# 05_-_DEBUGGING_PROGRAMMING.net
KiCad netlist of a schematic drawn in Altium Designer
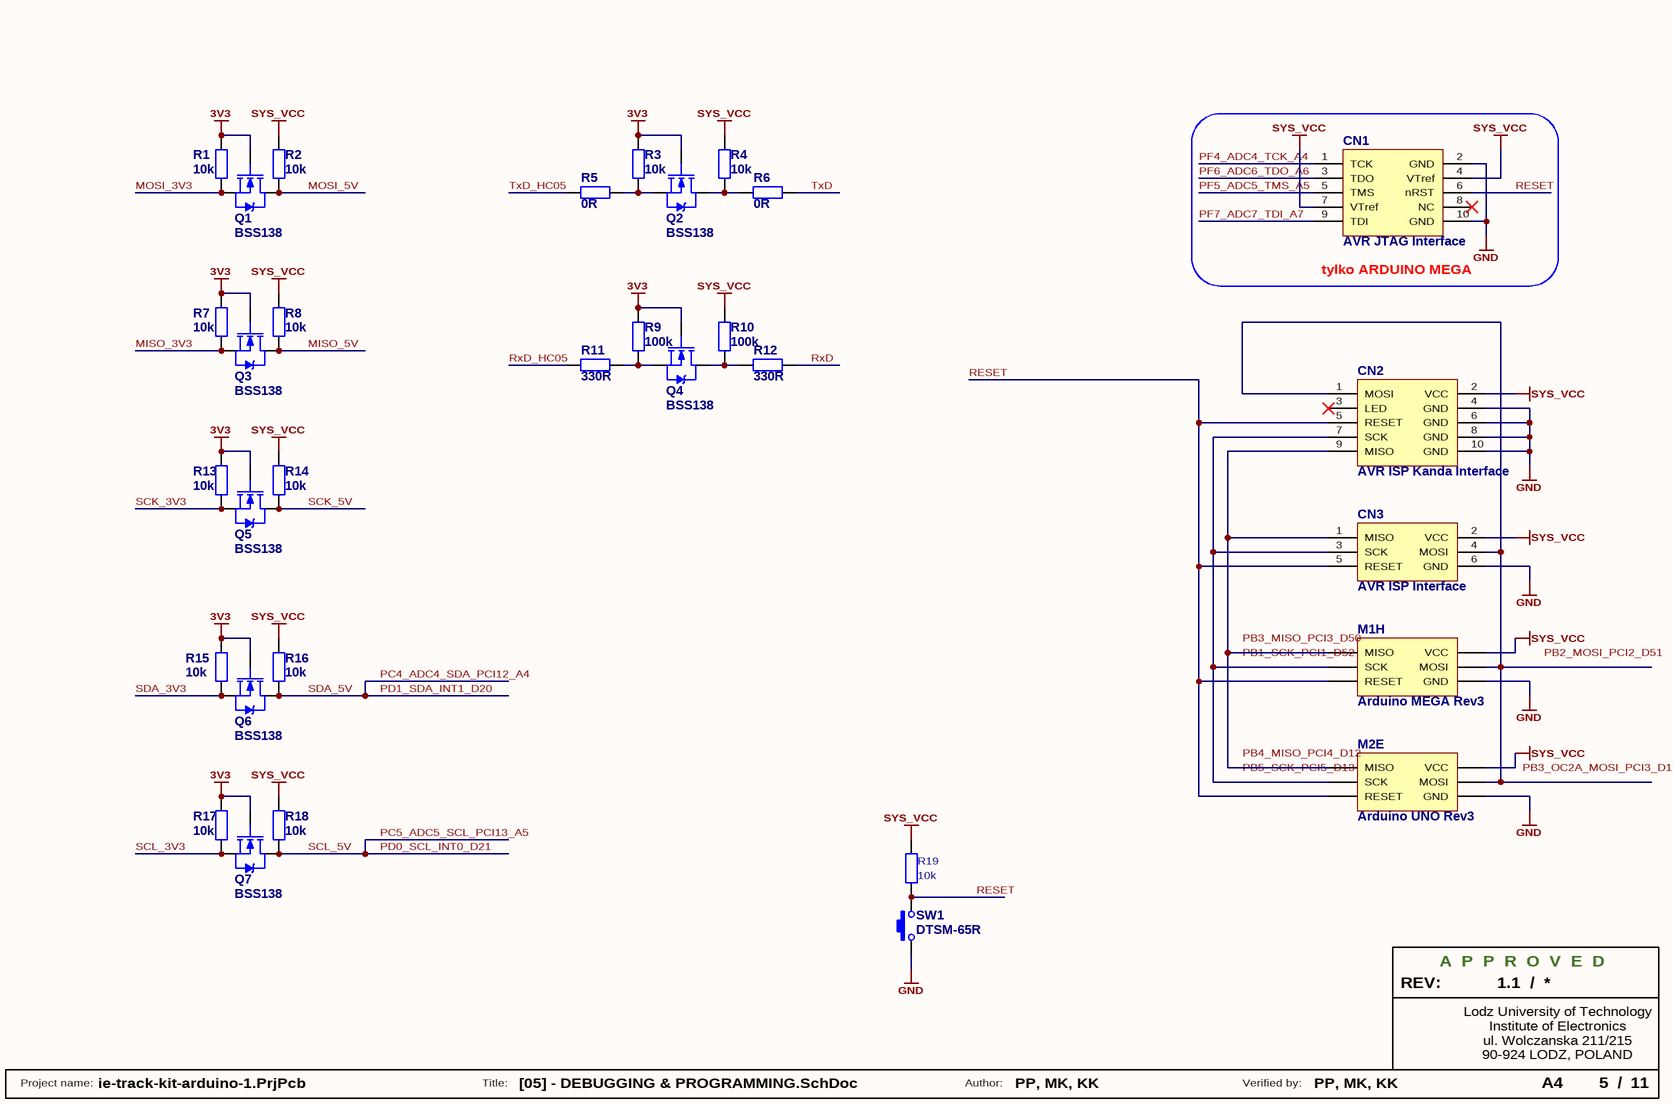
[diagram p0: [05] - DEBUGGING & PROGRAMMING.SchDoc]

(export (version "E")
  (design (tool "Eeschema 10.0.6"))
  (components
    (comp (ref "CN1")
      (value "AVR JTAG Interface")
      (footprint "IDC10")
      (description "JTAG Header for AVR MCU's")
      (libsource (lib "mcu_prog_and_debug_connectors") (part "AVR JTAG Interface"))
    )
    (comp (ref "CN2")
      (value "AVR ISP Kanda Interface")
      (footprint "IDC10")
      (description "Kanda ISP Programming Header for AVR MCU's")
      (libsource (lib "mcu_prog_and_debug_connectors") (part "AVR ISP Kanda Interface"))
    )
    (comp (ref "CN3")
      (value "AVR ISP Interface")
      (footprint "IDC6")
      (description "ISP Programming Header for AVR MCU's")
      (libsource (lib "mcu_prog_and_debug_connectors") (part "AVR ISP Interface"))
    )
    (comp (ref "M1")
      (value "Arduino MEGA Rev3")
      (footprint "Arduino_MEGA_UPSIDE_DOWN")
      (description "Arduino MEGA Rev3 Board")
      (libsource (lib "mcu_modules") (part "Arduino MEGA Rev3"))
    )
    (comp (ref "M2")
      (value "Arduino UNO Rev3")
      (footprint "Arduino_UNO_UPSIDE_DOWN")
      (description "Arduino UNO Rev3 Board")
      (libsource (lib "mcu_modules") (part "Arduino UNO Rev3"))
    )
    (comp (ref "Q1")
      (value "BSS138")
      (footprint "SOT-23")
      (description "N-Channel Enhancement Mode Vertical DMOS FET")
      (fields (field (name "PUBLISHER") "Altium Limited"))
      (libsource (lib "transistors_other") (part "BSS138"))
    )
    (comp (ref "Q2")
      (value "BSS138")
      (footprint "SOT-23")
      (description "N-Channel Enhancement Mode Vertical DMOS FET")
      (fields (field (name "PUBLISHER") "Altium Limited"))
      (libsource (lib "transistors_mos") (part "BSS138"))
    )
    (comp (ref "Q3")
      (value "BSS138")
      (footprint "SOT-23")
      (description "N-Channel Enhancement Mode Vertical DMOS FET")
      (fields (field (name "PUBLISHER") "Altium Limited"))
      (libsource (lib "transistors_other") (part "BSS138"))
    )
    (comp (ref "Q4")
      (value "BSS138")
      (footprint "SOT-23")
      (description "N-Channel Enhancement Mode Vertical DMOS FET")
      (fields (field (name "PUBLISHER") "Altium Limited"))
      (libsource (lib "transistors_mos") (part "BSS138"))
    )
    (comp (ref "Q5")
      (value "BSS138")
      (footprint "SOT-23")
      (description "N-Channel Enhancement Mode Vertical DMOS FET")
      (fields (field (name "PUBLISHER") "Altium Limited"))
      (libsource (lib "transistors_other") (part "BSS138"))
    )
    (comp (ref "Q6")
      (value "BSS138")
      (footprint "SOT-23")
      (description "N-Channel Enhancement Mode Vertical DMOS FET")
      (fields (field (name "PUBLISHER") "Altium Limited"))
      (libsource (lib "transistors_other") (part "BSS138"))
    )
    (comp (ref "Q7")
      (value "BSS138")
      (footprint "SOT-23")
      (description "N-Channel Enhancement Mode Vertical DMOS FET")
      (fields (field (name "PUBLISHER") "Altium Limited"))
      (libsource (lib "transistors_other") (part "BSS138"))
    )
    (comp (ref "R1")
      (value "10k")
      (footprint "R0805")
      (description "Resistor")
      (libsource (lib "resistors") (part "Res"))
    )
    (comp (ref "R2")
      (value "10k")
      (footprint "R0805")
      (description "Resistor")
      (libsource (lib "resistors") (part "Res"))
    )
    (comp (ref "R3")
      (value "10k")
      (footprint "R0805")
      (description "Resistor")
      (libsource (lib "") (part "Res_2"))
    )
    (comp (ref "R4")
      (value "10k")
      (footprint "R0805")
      (description "Resistor")
      (libsource (lib "") (part "Res_2"))
    )
    (comp (ref "R5")
      (value "0R")
      (footprint "R0805")
      (description "Resistor")
      (libsource (lib "") (part "Res_1"))
    )
    (comp (ref "R6")
      (value "0R")
      (footprint "R0805")
      (description "Resistor")
      (libsource (lib "") (part "Res_1"))
    )
    (comp (ref "R7")
      (value "10k")
      (footprint "R0805")
      (description "Resistor")
      (libsource (lib "resistors") (part "Res"))
    )
    (comp (ref "R8")
      (value "10k")
      (footprint "R0805")
      (description "Resistor")
      (libsource (lib "resistors") (part "Res"))
    )
    (comp (ref "R9")
      (value "100k")
      (footprint "R0805")
      (description "Resistor")
      (libsource (lib "") (part "Res_2"))
    )
    (comp (ref "R10")
      (value "100k")
      (footprint "R0805")
      (description "Resistor")
      (libsource (lib "") (part "Res_2"))
    )
    (comp (ref "R11")
      (value "330R")
      (footprint "R0805")
      (description "Resistor")
      (libsource (lib "") (part "Res_1"))
    )
    (comp (ref "R12")
      (value "330R")
      (footprint "R0805")
      (description "Resistor")
      (libsource (lib "") (part "Res_1"))
    )
    (comp (ref "R13")
      (value "10k")
      (footprint "R0805")
      (description "Resistor")
      (libsource (lib "resistors") (part "Res"))
    )
    (comp (ref "R14")
      (value "10k")
      (footprint "R0805")
      (description "Resistor")
      (libsource (lib "resistors") (part "Res"))
    )
    (comp (ref "R15")
      (value "10k")
      (footprint "R0805")
      (description "Resistor")
      (libsource (lib "resistors") (part "Res"))
    )
    (comp (ref "R16")
      (value "10k")
      (footprint "R0805")
      (description "Resistor")
      (libsource (lib "resistors") (part "Res"))
    )
    (comp (ref "R17")
      (value "10k")
      (footprint "R0805")
      (description "Resistor")
      (libsource (lib "resistors") (part "Res"))
    )
    (comp (ref "R18")
      (value "10k")
      (footprint "R0805")
      (description "Resistor")
      (libsource (lib "resistors") (part "Res"))
    )
    (comp (ref "R19")
      (value "10k")
      (footprint "R0805")
      (description "Resistor")
      (libsource (lib "") (part "Res_3"))
    )
    (comp (ref "SW1")
      (value "DTSM-65R")
      (footprint "DTSM-65R")
      (description "DIPTRONICS Red 6x6mm SMD Tactile SPST-NO Switch")
      (libsource (lib "microswitches") (part "DTSM-65R"))
    )
  )
  (nets
    (net (code "1") (name "/MISO_3V3") (class "Default")
      (node (ref "Q3") (pin "2") (pinfunction "S_2") (pintype "passive"))
      (node (ref "R7") (pin "1") (pinfunction "1_1") (pintype "passive"))
    )
    (net (code "2") (name "/MISO_5V") (class "Default")
      (node (ref "Q3") (pin "3") (pinfunction "D_3") (pintype "passive"))
      (node (ref "R8") (pin "1") (pinfunction "1_1") (pintype "passive"))
    )
    (net (code "3") (name "/MOSI_3V3") (class "Default")
      (node (ref "Q1") (pin "2") (pinfunction "S_2") (pintype "passive"))
      (node (ref "R1") (pin "1") (pinfunction "1_1") (pintype "passive"))
    )
    (net (code "4") (name "/MOSI_5V") (class "Default")
      (node (ref "Q1") (pin "3") (pinfunction "D_3") (pintype "passive"))
      (node (ref "R2") (pin "1") (pinfunction "1_1") (pintype "passive"))
    )
    (net (code "11") (name "/PC4_ADC4_SDA_PCI12_A4") (class "Default")
      (node (ref "Q6") (pin "3") (pinfunction "D_3") (pintype "passive"))
      (node (ref "R16") (pin "1") (pinfunction "1_1") (pintype "passive"))
    )
    (net (code "12") (name "/PC5_ADC5_SCL_PCI13_A5") (class "Default")
      (node (ref "Q7") (pin "3") (pinfunction "D_3") (pintype "passive"))
      (node (ref "R18") (pin "1") (pinfunction "1_1") (pintype "passive"))
    )
    (net (code "13") (name "/PF4_ADC4_TCK_A4") (class "Default")
      (node (ref "CN1") (pin "1") (pinfunction "TCK_1") (pintype "passive"))
    )
    (net (code "14") (name "/PF5_ADC5_TMS_A5") (class "Default")
      (node (ref "CN1") (pin "5") (pinfunction "TMS_5") (pintype "passive"))
    )
    (net (code "15") (name "/PF6_ADC6_TDO_A6") (class "Default")
      (node (ref "CN1") (pin "3") (pinfunction "TDO_3") (pintype "passive"))
    )
    (net (code "16") (name "/PF7_ADC7_TDI_A7") (class "Default")
      (node (ref "CN1") (pin "9") (pinfunction "TDI_9") (pintype "passive"))
    )
    (net (code "17") (name "/RESET") (class "Default")
      (node (ref "CN1") (pin "6") (pinfunction "nRST_6") (pintype "passive"))
      (node (ref "CN2") (pin "5") (pinfunction "RESET_5") (pintype "passive"))
      (node (ref "CN3") (pin "5") (pinfunction "RESET_5") (pintype "passive"))
      (node (ref "M1") (pin "PROG5") (pinfunction "RESET_PROG5") (pintype "passive"))
      (node (ref "M2") (pin "PROG5") (pinfunction "RESET_PROG5") (pintype "passive"))
      (node (ref "R19") (pin "1") (pinfunction "1_1") (pintype "passive"))
      (node (ref "SW1") (pin "2") (pinfunction "2_2") (pintype "passive"))
    )
    (net (code "18") (name "/RxD") (class "Default")
      (node (ref "R12") (pin "2") (pinfunction "2_2") (pintype "passive"))
    )
    (net (code "19") (name "/RxD_HC05") (class "Default")
      (node (ref "R11") (pin "1") (pinfunction "1_1") (pintype "passive"))
    )
    (net (code "20") (name "/SCK_3V3") (class "Default")
      (node (ref "Q5") (pin "2") (pinfunction "S_2") (pintype "passive"))
      (node (ref "R13") (pin "1") (pinfunction "1_1") (pintype "passive"))
    )
    (net (code "21") (name "/SCK_5V") (class "Default")
      (node (ref "Q5") (pin "3") (pinfunction "D_3") (pintype "passive"))
      (node (ref "R14") (pin "1") (pinfunction "1_1") (pintype "passive"))
    )
    (net (code "22") (name "/SCL_3V3") (class "Default")
      (node (ref "Q7") (pin "2") (pinfunction "S_2") (pintype "passive"))
      (node (ref "R17") (pin "1") (pinfunction "1_1") (pintype "passive"))
    )
    (net (code "23") (name "/SDA_3V3") (class "Default")
      (node (ref "Q6") (pin "2") (pinfunction "S_2") (pintype "passive"))
      (node (ref "R15") (pin "1") (pinfunction "1_1") (pintype "passive"))
    )
    (net (code "24") (name "/TxD") (class "Default")
      (node (ref "R6") (pin "2") (pinfunction "2_2") (pintype "passive"))
    )
    (net (code "25") (name "/TxD_HC05") (class "Default")
      (node (ref "R5") (pin "1") (pinfunction "1_1") (pintype "passive"))
    )
    (net (code "26") (name "3V3") (class "Default")
      (node (ref "Q1") (pin "1") (pinfunction "G_1") (pintype "passive"))
      (node (ref "Q2") (pin "1") (pinfunction "G_1") (pintype "passive"))
      (node (ref "Q3") (pin "1") (pinfunction "G_1") (pintype "passive"))
      (node (ref "Q4") (pin "1") (pinfunction "G_1") (pintype "passive"))
      (node (ref "Q5") (pin "1") (pinfunction "G_1") (pintype "passive"))
      (node (ref "Q6") (pin "1") (pinfunction "G_1") (pintype "passive"))
      (node (ref "Q7") (pin "1") (pinfunction "G_1") (pintype "passive"))
      (node (ref "R1") (pin "2") (pinfunction "2_2") (pintype "passive"))
      (node (ref "R13") (pin "2") (pinfunction "2_2") (pintype "passive"))
      (node (ref "R15") (pin "2") (pinfunction "2_2") (pintype "passive"))
      (node (ref "R17") (pin "2") (pinfunction "2_2") (pintype "passive"))
      (node (ref "R3") (pin "1") (pinfunction "1_1") (pintype "passive"))
      (node (ref "R7") (pin "2") (pinfunction "2_2") (pintype "passive"))
      (node (ref "R9") (pin "1") (pinfunction "1_1") (pintype "passive"))
    )
    (net (code "27") (name "GND") (class "Default")
      (node (ref "CN1") (pin "10") (pinfunction "GND_10") (pintype "passive"))
      (node (ref "CN1") (pin "2") (pinfunction "GND_2") (pintype "passive"))
      (node (ref "CN2") (pin "10") (pinfunction "GND_10") (pintype "passive"))
      (node (ref "CN2") (pin "4") (pinfunction "GND_4") (pintype "passive"))
      (node (ref "CN2") (pin "6") (pinfunction "GND_6") (pintype "passive"))
      (node (ref "CN2") (pin "8") (pinfunction "GND_8") (pintype "passive"))
      (node (ref "CN3") (pin "6") (pinfunction "GND_6") (pintype "passive"))
      (node (ref "M1") (pin "PROG6") (pinfunction "GND_PROG6") (pintype "passive"))
      (node (ref "M2") (pin "PROG6") (pinfunction "GND_PROG6") (pintype "passive"))
      (node (ref "SW1") (pin "1") (pinfunction "1_1") (pintype "passive"))
    )
    (net (code "28") (name "Net-(CN2-MISO)") (class "Default")
      (node (ref "CN2") (pin "9") (pinfunction "MISO_9") (pintype "passive"))
      (node (ref "CN3") (pin "1") (pinfunction "MISO_1") (pintype "passive"))
      (node (ref "M1") (pin "PROG1") (pinfunction "MISO_PROG1") (pintype "passive"))
      (node (ref "M2") (pin "PROG1") (pinfunction "MISO_PROG1") (pintype "passive"))
    )
    (net (code "29") (name "Net-(CN2-MOSI)") (class "Default")
      (node (ref "CN2") (pin "1") (pinfunction "MOSI_1") (pintype "passive"))
      (node (ref "CN3") (pin "4") (pinfunction "MOSI_4") (pintype "passive"))
      (node (ref "M1") (pin "PROG4") (pinfunction "MOSI_PROG4") (pintype "passive"))
      (node (ref "M2") (pin "PROG4") (pinfunction "MOSI_PROG4") (pintype "passive"))
    )
    (net (code "30") (name "Net-(CN2-SCK)") (class "Default")
      (node (ref "CN2") (pin "7") (pinfunction "SCK_7") (pintype "passive"))
      (node (ref "CN3") (pin "3") (pinfunction "SCK_3") (pintype "passive"))
      (node (ref "M1") (pin "PROG3") (pinfunction "SCK_PROG3") (pintype "passive"))
      (node (ref "M2") (pin "PROG3") (pinfunction "SCK_PROG3") (pintype "passive"))
    )
    (net (code "31") (name "Net-(Q2-D)") (class "Default")
      (node (ref "Q2") (pin "3") (pinfunction "D_3") (pintype "passive"))
      (node (ref "R4") (pin "2") (pinfunction "2_2") (pintype "passive"))
      (node (ref "R6") (pin "1") (pinfunction "1_1") (pintype "passive"))
    )
    (net (code "32") (name "Net-(Q2-S)") (class "Default")
      (node (ref "Q2") (pin "2") (pinfunction "S_2") (pintype "passive"))
      (node (ref "R3") (pin "2") (pinfunction "2_2") (pintype "passive"))
      (node (ref "R5") (pin "2") (pinfunction "2_2") (pintype "passive"))
    )
    (net (code "33") (name "Net-(Q4-D)") (class "Default")
      (node (ref "Q4") (pin "3") (pinfunction "D_3") (pintype "passive"))
      (node (ref "R10") (pin "2") (pinfunction "2_2") (pintype "passive"))
      (node (ref "R12") (pin "1") (pinfunction "1_1") (pintype "passive"))
    )
    (net (code "34") (name "Net-(Q4-S)") (class "Default")
      (node (ref "Q4") (pin "2") (pinfunction "S_2") (pintype "passive"))
      (node (ref "R11") (pin "2") (pinfunction "2_2") (pintype "passive"))
      (node (ref "R9") (pin "2") (pinfunction "2_2") (pintype "passive"))
    )
    (net (code "35") (name "SYS_VCC") (class "Default")
      (node (ref "CN1") (pin "4") (pinfunction "VTref_4") (pintype "passive"))
      (node (ref "CN1") (pin "7") (pinfunction "VTref_7") (pintype "passive"))
      (node (ref "CN2") (pin "2") (pinfunction "VCC_2") (pintype "passive"))
      (node (ref "CN3") (pin "2") (pinfunction "VCC_2") (pintype "passive"))
      (node (ref "M1") (pin "PROG2") (pinfunction "VCC_PROG2") (pintype "passive"))
      (node (ref "M2") (pin "PROG2") (pinfunction "VCC_PROG2") (pintype "passive"))
      (node (ref "R10") (pin "1") (pinfunction "1_1") (pintype "passive"))
      (node (ref "R14") (pin "2") (pinfunction "2_2") (pintype "passive"))
      (node (ref "R16") (pin "2") (pinfunction "2_2") (pintype "passive"))
      (node (ref "R18") (pin "2") (pinfunction "2_2") (pintype "passive"))
      (node (ref "R19") (pin "2") (pinfunction "2_2") (pintype "passive"))
      (node (ref "R2") (pin "2") (pinfunction "2_2") (pintype "passive"))
      (node (ref "R4") (pin "1") (pinfunction "1_1") (pintype "passive"))
      (node (ref "R8") (pin "2") (pinfunction "2_2") (pintype "passive"))
    )
    (net (code "36") (name "unconnected-(CN1-NC-Pad8)") (class "Default")
      (node (ref "CN1") (pin "8") (pinfunction "NC_8") (pintype "passive+no_connect"))
    )
    (net (code "37") (name "unconnected-(CN2-LED-Pad3)") (class "Default")
      (node (ref "CN2") (pin "3") (pinfunction "LED_3") (pintype "passive+no_connect"))
    )
  )
)
